# BLDC_Sch.net
KiCad netlist of a schematic drawn in Altium Designer
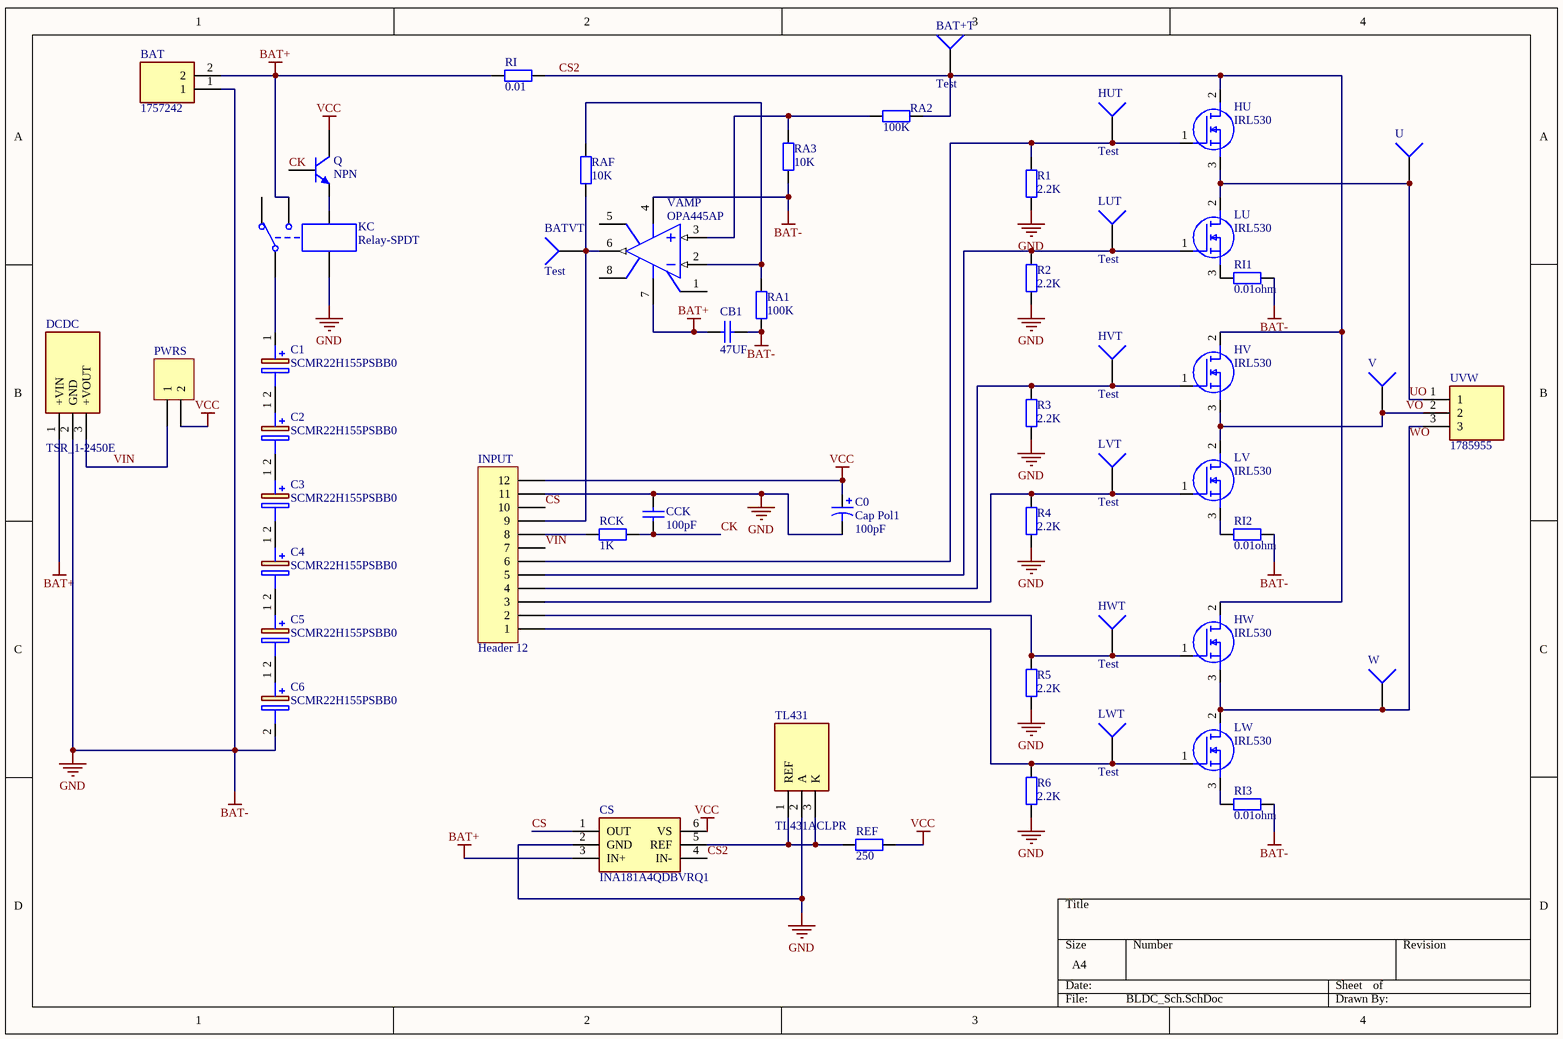
[diagram p0: BLDC_Sch.SchDoc]

(export (version "E")
  (design (tool "Eeschema 10.0.6"))
  (components
    (comp (ref "BAT")
      (value "1757242")
      (footprint "Comp_PCB:SHDR2W100P0X508_1X2_1016X860X1250P")
      (description "Connector")
      (fields
        (field (name "MANUFACTURER_PART_NUMBER") "OQ025A000000G")
        (field (name "MOUSER PART NUMBER") "523-OQ025A000000G")
      )
      (libsource (lib "Comp_Schm") (part "OQ025A000000G"))
    )
    (comp (ref "BAT+T")
      (value "Test")
      (footprint "PIN1")
      (description "Socket")
      (fields (field (name "PUBLISHER") "Altium Limited"))
      (libsource (lib "Miscellaneous Connectors") (part "Socket"))
    )
    (comp (ref "BATVT")
      (value "Test")
      (footprint "PIN1")
      (description "Socket")
      (fields (field (name "PUBLISHER") "Altium Limited"))
      (libsource (lib "Miscellaneous Connectors") (part "Socket"))
    )
    (comp (ref "C0")
      (value "Cap Pol1")
      (footprint "CAP 5.0*10*12.5")
      (description "Polarized Capacitor (Radial)")
      (fields (field (name "ALTIUM_VALUE") "100pF") (field (name "PUBLISHER") "Altium Limited"))
      (libsource (lib "Miscellaneous Devices") (part "Cap Pol1"))
    )
    (comp (ref "C1")
      (value "SCMR22H155PSBB0")
      (footprint "Comp_PCB:SCMR22H155PSBB0")
      (description "Capacitor Polarised")
      (fields (field (name "MOUSER PART NUMBER") "581-SCMR22H155PSBB0"))
      (libsource (lib "Comp_Schm") (part "SCMR22H155PSBB0"))
    )
    (comp (ref "C2")
      (value "SCMR22H155PSBB0")
      (footprint "Comp_PCB:SCMR22H155PSBB0")
      (description "Capacitor Polarised")
      (fields (field (name "MOUSER PART NUMBER") "581-SCMR22H155PSBB0"))
      (libsource (lib "Comp_Schm") (part "SCMR22H155PSBB0"))
    )
    (comp (ref "C3")
      (value "SCMR22H155PSBB0")
      (footprint "Comp_PCB:SCMR22H155PSBB0")
      (description "Capacitor Polarised")
      (fields (field (name "MOUSER PART NUMBER") "581-SCMR22H155PSBB0"))
      (libsource (lib "Comp_Schm") (part "SCMR22H155PSBB0"))
    )
    (comp (ref "C4")
      (value "SCMR22H155PSBB0")
      (footprint "Comp_PCB:SCMR22H155PSBB0")
      (description "Capacitor Polarised")
      (fields (field (name "MOUSER PART NUMBER") "581-SCMR22H155PSBB0"))
      (libsource (lib "Comp_Schm") (part "SCMR22H155PSBB0"))
    )
    (comp (ref "C5")
      (value "SCMR22H155PSBB0")
      (footprint "Comp_PCB:SCMR22H155PSBB0")
      (description "Capacitor Polarised")
      (fields (field (name "MOUSER PART NUMBER") "581-SCMR22H155PSBB0"))
      (libsource (lib "Comp_Schm") (part "SCMR22H155PSBB0"))
    )
    (comp (ref "C6")
      (value "SCMR22H155PSBB0")
      (footprint "Comp_PCB:SCMR22H155PSBB0")
      (description "Capacitor Polarised")
      (fields (field (name "MOUSER PART NUMBER") "581-SCMR22H155PSBB0"))
      (libsource (lib "Comp_Schm") (part "SCMR22H155PSBB0"))
    )
    (comp (ref "CB1")
      (value "47UF")
      (footprint "CBB 6.3*6.3*5")
      (description "Capacitor")
      (fields (field (name "Comment") "Cap") (field (name "PUBLISHER") "Altium Limited"))
      (libsource (lib "Miscellaneous Devices") (part "Cap"))
    )
    (comp (ref "CCK")
      (value "100pF")
      (footprint "CBB 6.3*6.3*5")
      (description "Capacitor")
      (fields (field (name "Comment") "Cap") (field (name "PUBLISHER") "Altium Limited"))
      (libsource (lib "Miscellaneous Devices") (part "Cap"))
    )
    (comp (ref "CS")
      (value "INA181A4QDBVRQ1")
      (footprint "Comp_PCB:SOT95P280X145-6N")
      (description "Integrated Circuit")
      (fields (field (name "MOUSER PART NUMBER") "595-INA181A4QDBVRQ1"))
      (libsource (lib "*") (part "INA181A4QDBVRQ1"))
    )
    (comp (ref "DCDC")
      (value "TSR_1-2450E")
      (footprint "Comp_PCB:TSR12450E")
      (description "Power Supply")
      (fields
        (field (name "MANUFACTURER_PART_NUMBER") "TSR 1-2450E")
        (field (name "MOUSER PART NUMBER") "495-TSR1-2450E")
      )
      (libsource (lib "*") (part "TSR_1-2450E"))
    )
    (comp (ref "HU")
      (value "IRL530")
      (footprint "Comp_PCB:TO254P465X1024X2050-3P")
      (description "MOSFET (N-Channel)")
      (fields (field (name "MOUSER PART NUMBER") "844-IRL530"))
      (libsource (lib "Comp_Schm") (part "IRL530"))
    )
    (comp (ref "HUT")
      (value "Test")
      (footprint "PIN1")
      (description "Socket")
      (fields (field (name "PUBLISHER") "Altium Limited"))
      (libsource (lib "Miscellaneous Connectors") (part "Socket"))
    )
    (comp (ref "HV")
      (value "IRL530")
      (footprint "Comp_PCB:TO254P465X1024X2050-3P")
      (description "MOSFET (N-Channel)")
      (fields (field (name "MOUSER PART NUMBER") "844-IRL530"))
      (libsource (lib "Comp_Schm") (part "IRL530"))
    )
    (comp (ref "HVT")
      (value "Test")
      (footprint "PIN1")
      (description "Socket")
      (fields (field (name "PUBLISHER") "Altium Limited"))
      (libsource (lib "Miscellaneous Connectors") (part "Socket"))
    )
    (comp (ref "HW")
      (value "IRL530")
      (footprint "Comp_PCB:TO254P465X1024X2050-3P")
      (description "MOSFET (N-Channel)")
      (fields (field (name "MOUSER PART NUMBER") "844-IRL530"))
      (libsource (lib "Comp_Schm") (part "IRL530"))
    )
    (comp (ref "HWT")
      (value "Test")
      (footprint "PIN1")
      (description "Socket")
      (fields (field (name "PUBLISHER") "Altium Limited"))
      (libsource (lib "Miscellaneous Connectors") (part "Socket"))
    )
    (comp (ref "INPUT")
      (value "Header 12")
      (footprint "HDR1X12")
      (description "Header, 12-Pin")
      (fields (field (name "PUBLISHER") "Altium Limited"))
      (libsource (lib "Miscellaneous Connectors") (part "Header 12"))
    )
    (comp (ref "KC")
      (value "Relay-SPDT")
      (footprint "SRD-C_BK")
      (description "Single-Pole Dual-Throw Relay")
      (fields (field (name "PUBLISHER") "Altium Limited"))
      (libsource (lib "Miscellaneous Devices") (part "Relay-SPDT"))
    )
    (comp (ref "LU")
      (value "IRL530")
      (footprint "Comp_PCB:TO254P465X1024X2050-3P")
      (description "MOSFET (N-Channel)")
      (fields (field (name "MOUSER PART NUMBER") "844-IRL530"))
      (libsource (lib "Comp_Schm") (part "IRL530"))
    )
    (comp (ref "LUT")
      (value "Test")
      (footprint "PIN1")
      (description "Socket")
      (fields (field (name "PUBLISHER") "Altium Limited"))
      (libsource (lib "Miscellaneous Connectors") (part "Socket"))
    )
    (comp (ref "LV")
      (value "IRL530")
      (footprint "Comp_PCB:TO254P465X1024X2050-3P")
      (description "MOSFET (N-Channel)")
      (fields (field (name "MOUSER PART NUMBER") "844-IRL530"))
      (libsource (lib "Comp_Schm") (part "IRL530"))
    )
    (comp (ref "LVT")
      (value "Test")
      (footprint "PIN1")
      (description "Socket")
      (fields (field (name "PUBLISHER") "Altium Limited"))
      (libsource (lib "Miscellaneous Connectors") (part "Socket"))
    )
    (comp (ref "LW")
      (value "IRL530")
      (footprint "Comp_PCB:TO254P465X1024X2050-3P")
      (description "MOSFET (N-Channel)")
      (fields (field (name "MOUSER PART NUMBER") "844-IRL530"))
      (libsource (lib "Comp_Schm") (part "IRL530"))
    )
    (comp (ref "LWT")
      (value "Test")
      (footprint "PIN1")
      (description "Socket")
      (fields (field (name "PUBLISHER") "Altium Limited"))
      (libsource (lib "Miscellaneous Connectors") (part "Socket"))
    )
    (comp (ref "PWRS")
      (value "Header 2")
      (footprint "HDR1X2")
      (description "Header, 2-Pin")
      (fields (field (name "PUBLISHER") "Altium Limited"))
      (libsource (lib "Miscellaneous Connectors") (part "Header 2"))
    )
    (comp (ref "Q")
      (value "NPN")
      (footprint "TO-226-AA")
      (description "NPN Bipolar Transistor")
      (fields (field (name "PUBLISHER") "Altium Limited"))
      (libsource (lib "Miscellaneous Devices") (part "NPN"))
    )
    (comp (ref "R1")
      (value "2.2K")
      (footprint "RS 1/4W")
      (description "Resistor")
      (fields (field (name "Comment") "Res2") (field (name "PUBLISHER") "Altium Limited"))
      (libsource (lib "") (part "Res2_2"))
    )
    (comp (ref "R2")
      (value "2.2K")
      (footprint "RS 1/4W")
      (description "Resistor")
      (fields (field (name "Comment") "Res2") (field (name "PUBLISHER") "Altium Limited"))
      (libsource (lib "") (part "Res2_2"))
    )
    (comp (ref "R3")
      (value "2.2K")
      (footprint "RS 1/4W")
      (description "Resistor")
      (fields (field (name "Comment") "Res2") (field (name "PUBLISHER") "Altium Limited"))
      (libsource (lib "") (part "Res2_2"))
    )
    (comp (ref "R4")
      (value "2.2K")
      (footprint "RS 1/4W")
      (description "Resistor")
      (fields (field (name "Comment") "Res2") (field (name "PUBLISHER") "Altium Limited"))
      (libsource (lib "") (part "Res2_1"))
    )
    (comp (ref "R5")
      (value "2.2K")
      (footprint "RS 1/4W")
      (description "Resistor")
      (fields (field (name "Comment") "Res2") (field (name "PUBLISHER") "Altium Limited"))
      (libsource (lib "") (part "Res2_1"))
    )
    (comp (ref "R6")
      (value "2.2K")
      (footprint "RS 1/4W")
      (description "Resistor")
      (fields (field (name "Comment") "Res2") (field (name "PUBLISHER") "Altium Limited"))
      (libsource (lib "") (part "Res2_1"))
    )
    (comp (ref "RA1")
      (value "100K")
      (footprint "RS 1/4W")
      (description "Resistor")
      (fields (field (name "Comment") "Res2") (field (name "PUBLISHER") "Altium Limited"))
      (libsource (lib "") (part "Res2_1"))
    )
    (comp (ref "RA2")
      (value "100K")
      (footprint "RS 1/4W")
      (description "Resistor")
      (fields (field (name "Comment") "Res2") (field (name "PUBLISHER") "Altium Limited"))
      (libsource (lib "Miscellaneous Devices") (part "Res2"))
    )
    (comp (ref "RA3")
      (value "10K")
      (footprint "RS 1/4W")
      (description "Resistor")
      (fields (field (name "Comment") "Res2") (field (name "PUBLISHER") "Altium Limited"))
      (libsource (lib "") (part "Res2_2"))
    )
    (comp (ref "RAF")
      (value "10K")
      (footprint "RS 1/4W")
      (description "Resistor")
      (fields (field (name "Comment") "Res2") (field (name "PUBLISHER") "Altium Limited"))
      (libsource (lib "") (part "Res2_2"))
    )
    (comp (ref "RCK")
      (value "1K")
      (footprint "RS 1/4W")
      (description "Resistor")
      (fields (field (name "Comment") "Res2") (field (name "PUBLISHER") "Altium Limited"))
      (libsource (lib "Miscellaneous Devices") (part "Res2"))
    )
    (comp (ref "REF")
      (value "250")
      (footprint "RS 1/4W")
      (description "Resistor")
      (fields (field (name "Comment") "Res2") (field (name "PUBLISHER") "Altium Limited"))
      (libsource (lib "Miscellaneous Devices") (part "Res2"))
    )
    (comp (ref "RI")
      (value "0.01")
      (footprint "R 2512")
      (description "Resistor")
      (fields (field (name "Comment") "Res2") (field (name "PUBLISHER") "Altium Limited"))
      (libsource (lib "Miscellaneous Devices") (part "Res2"))
    )
    (comp (ref "RI1")
      (value "0.01ohm")
      (footprint "R 2512")
      (description "Resistor")
      (fields (field (name "Comment") "Res2") (field (name "PUBLISHER") "Altium Limited"))
      (libsource (lib "Miscellaneous Devices") (part "Res2"))
    )
    (comp (ref "RI2")
      (value "0.01ohm")
      (footprint "R 2512")
      (description "Resistor")
      (fields (field (name "Comment") "Res2") (field (name "PUBLISHER") "Altium Limited"))
      (libsource (lib "Miscellaneous Devices") (part "Res2"))
    )
    (comp (ref "RI3")
      (value "0.01ohm")
      (footprint "R 2512")
      (description "Resistor")
      (fields (field (name "Comment") "Res2") (field (name "PUBLISHER") "Altium Limited"))
      (libsource (lib "Miscellaneous Devices") (part "Res2"))
    )
    (comp (ref "TL431")
      (value "TL431ACLPR")
      (footprint "Comp_PCB:TL431ACLPR")
      (description "Integrated Circuit")
      (fields (field (name "MOUSER PART NUMBER") "595-TL431ACLPR"))
      (libsource (lib "Comp_Schm") (part "TL431ACLPR"))
    )
    (comp (ref "U")
      (value "2376595-2")
      (footprint "23765952")
      (description "Socket")
      (fields (field (name "PUBLISHER") "Altium Limited"))
      (libsource (lib "Miscellaneous Connectors") (part "Socket"))
    )
    (comp (ref "UVW")
      (value "1785955")
      (footprint "Comp_PCB:SHDRRA3W103P0X508_1X3_1524X1200X872P")
      (description "Connector")
      (fields
        (field (name "MANUFACTURER_PART_NUMBER") "1759020")
        (field (name "MOUSER PART NUMBER") "651-1759020")
      )
      (libsource (lib "*") (part "1759020"))
    )
    (comp (ref "V")
      (value "2376595-2")
      (footprint "23765952")
      (description "Socket")
      (fields (field (name "PUBLISHER") "Altium Limited"))
      (libsource (lib "Miscellaneous Connectors") (part "Socket"))
    )
    (comp (ref "VAMP")
      (value "OPA445AP")
      (footprint "DIP794W53P254L959H508Q8N")
      (description "High Performance Operational Amplifier")
      (fields (field (name "PUBLISHER") "Altium Limited"))
      (libsource (lib "TI Operational Amplifier") (part "LM101AJG"))
    )
    (comp (ref "W")
      (value "2376595-2")
      (footprint "23765952")
      (description "Socket")
      (fields (field (name "PUBLISHER") "Altium Limited"))
      (libsource (lib "Miscellaneous Connectors") (part "Socket"))
    )
  )
  (nets
    (net (code "1") (name "/CK") (class "Default")
      (node (ref "CCK") (pin "1") (pinfunction "1_1") (pintype "passive"))
      (node (ref "Q") (pin "2") (pinfunction "B_2") (pintype "passive"))
      (node (ref "RCK") (pin "2") (pinfunction "2_2") (pintype "passive"))
    )
    (net (code "2") (name "/CS") (class "Default")
      (node (ref "CS") (pin "1") (pinfunction "OUT_1") (pintype "passive"))
      (node (ref "INPUT") (pin "10") (pinfunction "10_10") (pintype "passive"))
    )
    (net (code "3") (name "/CS2") (class "Default")
      (node (ref "BAT+T") (pin "1") (pinfunction "1_1") (pintype "passive"))
      (node (ref "CS") (pin "4") (pinfunction "IN-_4") (pintype "passive"))
      (node (ref "HU") (pin "2") (pinfunction "D_2") (pintype "passive"))
      (node (ref "HV") (pin "2") (pinfunction "D_2") (pintype "passive"))
      (node (ref "HW") (pin "2") (pinfunction "D_2") (pintype "passive"))
      (node (ref "RA2") (pin "2") (pinfunction "2_2") (pintype "passive"))
      (node (ref "RI") (pin "2") (pinfunction "2_2") (pintype "passive"))
    )
    (net (code "4") (name "/UO") (class "Default")
      (node (ref "HU") (pin "3") (pinfunction "S_3") (pintype "passive"))
      (node (ref "LU") (pin "2") (pinfunction "D_2") (pintype "passive"))
      (node (ref "U") (pin "1") (pinfunction "1_1") (pintype "passive"))
      (node (ref "UVW") (pin "1") (pinfunction "1_1") (pintype "passive"))
    )
    (net (code "5") (name "/VIN") (class "Default")
      (node (ref "DCDC") (pin "3") (pinfunction "+VOUT_3") (pintype "passive"))
      (node (ref "INPUT") (pin "7") (pinfunction "7_7") (pintype "passive"))
      (node (ref "PWRS") (pin "1") (pinfunction "1_1") (pintype "passive"))
    )
    (net (code "6") (name "/VO") (class "Default")
      (node (ref "HV") (pin "3") (pinfunction "S_3") (pintype "passive"))
      (node (ref "LV") (pin "2") (pinfunction "D_2") (pintype "passive"))
      (node (ref "UVW") (pin "2") (pinfunction "2_2") (pintype "passive"))
      (node (ref "V") (pin "1") (pinfunction "1_1") (pintype "passive"))
    )
    (net (code "7") (name "/WO") (class "Default")
      (node (ref "HW") (pin "3") (pinfunction "S_3") (pintype "passive"))
      (node (ref "LW") (pin "2") (pinfunction "D_2") (pintype "passive"))
      (node (ref "UVW") (pin "3") (pinfunction "3_3") (pintype "passive"))
      (node (ref "W") (pin "1") (pinfunction "1_1") (pintype "passive"))
    )
    (net (code "8") (name "BAT+") (class "Default")
      (node (ref "BAT") (pin "2") (pinfunction "2_2") (pintype "passive"))
      (node (ref "CB1") (pin "1") (pinfunction "1_1") (pintype "passive"))
      (node (ref "CS") (pin "3") (pinfunction "IN+_3") (pintype "passive"))
      (node (ref "DCDC") (pin "1") (pinfunction "+VIN_1") (pintype "passive"))
      (node (ref "KC") (pin "3") (pinfunction "3_3") (pintype "passive"))
      (node (ref "RI") (pin "1") (pinfunction "1_1") (pintype "passive"))
      (node (ref "VAMP") (pin "7") (pinfunction "V+_7") (pintype "power_in"))
    )
    (net (code "9") (name "BAT-") (class "Default")
      (node (ref "BAT") (pin "1") (pinfunction "1_1") (pintype "passive"))
      (node (ref "C0") (pin "2") (pinfunction "2_2") (pintype "passive"))
      (node (ref "C6") (pin "2") (pinfunction "-_2") (pintype "passive"))
      (node (ref "CB1") (pin "2") (pinfunction "2_2") (pintype "passive"))
      (node (ref "CCK") (pin "2") (pinfunction "2_2") (pintype "passive"))
      (node (ref "CS") (pin "2") (pinfunction "GND_2") (pintype "passive"))
      (node (ref "DCDC") (pin "2") (pinfunction "GND_2") (pintype "passive"))
      (node (ref "INPUT") (pin "11") (pinfunction "11_11") (pintype "passive"))
      (node (ref "KC") (pin "4") (pinfunction "4_4") (pintype "passive"))
      (node (ref "R1") (pin "1") (pinfunction "1_1") (pintype "passive"))
      (node (ref "R2") (pin "1") (pinfunction "1_1") (pintype "passive"))
      (node (ref "R3") (pin "1") (pinfunction "1_1") (pintype "passive"))
      (node (ref "R4") (pin "2") (pinfunction "2_2") (pintype "passive"))
      (node (ref "R5") (pin "2") (pinfunction "2_2") (pintype "passive"))
      (node (ref "R6") (pin "2") (pinfunction "2_2") (pintype "passive"))
      (node (ref "RA1") (pin "2") (pinfunction "2_2") (pintype "passive"))
      (node (ref "RA3") (pin "1") (pinfunction "1_1") (pintype "passive"))
      (node (ref "RI1") (pin "2") (pinfunction "2_2") (pintype "passive"))
      (node (ref "RI2") (pin "2") (pinfunction "2_2") (pintype "passive"))
      (node (ref "RI3") (pin "2") (pinfunction "2_2") (pintype "passive"))
      (node (ref "TL431") (pin "2") (pinfunction "A_2") (pintype "passive"))
      (node (ref "VAMP") (pin "4") (pinfunction "V-_4") (pintype "power_in"))
    )
    (net (code "10") (name "Net-(C1-+)") (class "Default")
      (node (ref "C1") (pin "1") (pinfunction "+_1") (pintype "passive"))
      (node (ref "KC") (pin "1") (pinfunction "1_1") (pintype "passive"))
    )
    (net (code "11") (name "Net-(C1--)") (class "Default")
      (node (ref "C1") (pin "2") (pinfunction "-_2") (pintype "passive"))
      (node (ref "C2") (pin "1") (pinfunction "+_1") (pintype "passive"))
    )
    (net (code "12") (name "Net-(C2--)") (class "Default")
      (node (ref "C2") (pin "2") (pinfunction "-_2") (pintype "passive"))
      (node (ref "C3") (pin "1") (pinfunction "+_1") (pintype "passive"))
    )
    (net (code "13") (name "Net-(C3--)") (class "Default")
      (node (ref "C3") (pin "2") (pinfunction "-_2") (pintype "passive"))
      (node (ref "C4") (pin "1") (pinfunction "+_1") (pintype "passive"))
    )
    (net (code "14") (name "Net-(C4--)") (class "Default")
      (node (ref "C4") (pin "2") (pinfunction "-_2") (pintype "passive"))
      (node (ref "C5") (pin "1") (pinfunction "+_1") (pintype "passive"))
    )
    (net (code "15") (name "Net-(C5--)") (class "Default")
      (node (ref "C5") (pin "2") (pinfunction "-_2") (pintype "passive"))
      (node (ref "C6") (pin "1") (pinfunction "+_1") (pintype "passive"))
    )
    (net (code "16") (name "Net-(CS-REF)") (class "Default")
      (node (ref "CS") (pin "5") (pinfunction "REF_5") (pintype "passive"))
      (node (ref "REF") (pin "1") (pinfunction "1_1") (pintype "passive"))
      (node (ref "TL431") (pin "1") (pinfunction "REF_1") (pintype "passive"))
      (node (ref "TL431") (pin "3") (pinfunction "K_3") (pintype "passive"))
    )
    (net (code "17") (name "Net-(HU-G)") (class "Default")
      (node (ref "HU") (pin "1") (pinfunction "G_1") (pintype "passive"))
      (node (ref "HUT") (pin "1") (pinfunction "1_1") (pintype "passive"))
      (node (ref "INPUT") (pin "6") (pinfunction "6_6") (pintype "passive"))
      (node (ref "R1") (pin "2") (pinfunction "2_2") (pintype "passive"))
    )
    (net (code "18") (name "Net-(HV-G)") (class "Default")
      (node (ref "HV") (pin "1") (pinfunction "G_1") (pintype "passive"))
      (node (ref "HVT") (pin "1") (pinfunction "1_1") (pintype "passive"))
      (node (ref "INPUT") (pin "4") (pinfunction "4_4") (pintype "passive"))
      (node (ref "R3") (pin "2") (pinfunction "2_2") (pintype "passive"))
    )
    (net (code "19") (name "Net-(HW-G)") (class "Default")
      (node (ref "HW") (pin "1") (pinfunction "G_1") (pintype "passive"))
      (node (ref "HWT") (pin "1") (pinfunction "1_1") (pintype "passive"))
      (node (ref "INPUT") (pin "2") (pinfunction "2_2") (pintype "passive"))
      (node (ref "R5") (pin "1") (pinfunction "1_1") (pintype "passive"))
    )
    (net (code "20") (name "Net-(INPUT-Pad8)") (class "Default")
      (node (ref "INPUT") (pin "8") (pinfunction "8_8") (pintype "passive"))
      (node (ref "RCK") (pin "1") (pinfunction "1_1") (pintype "passive"))
    )
    (net (code "21") (name "Net-(LU-G)") (class "Default")
      (node (ref "INPUT") (pin "5") (pinfunction "5_5") (pintype "passive"))
      (node (ref "LU") (pin "1") (pinfunction "G_1") (pintype "passive"))
      (node (ref "LUT") (pin "1") (pinfunction "1_1") (pintype "passive"))
      (node (ref "R2") (pin "2") (pinfunction "2_2") (pintype "passive"))
    )
    (net (code "22") (name "Net-(LU-S)") (class "Default")
      (node (ref "LU") (pin "3") (pinfunction "S_3") (pintype "passive"))
      (node (ref "RI1") (pin "1") (pinfunction "1_1") (pintype "passive"))
    )
    (net (code "23") (name "Net-(LV-G)") (class "Default")
      (node (ref "INPUT") (pin "3") (pinfunction "3_3") (pintype "passive"))
      (node (ref "LV") (pin "1") (pinfunction "G_1") (pintype "passive"))
      (node (ref "LVT") (pin "1") (pinfunction "1_1") (pintype "passive"))
      (node (ref "R4") (pin "1") (pinfunction "1_1") (pintype "passive"))
    )
    (net (code "24") (name "Net-(LV-S)") (class "Default")
      (node (ref "LV") (pin "3") (pinfunction "S_3") (pintype "passive"))
      (node (ref "RI2") (pin "1") (pinfunction "1_1") (pintype "passive"))
    )
    (net (code "25") (name "Net-(LW-G)") (class "Default")
      (node (ref "INPUT") (pin "1") (pinfunction "1_1") (pintype "passive"))
      (node (ref "LW") (pin "1") (pinfunction "G_1") (pintype "passive"))
      (node (ref "LWT") (pin "1") (pinfunction "1_1") (pintype "passive"))
      (node (ref "R6") (pin "1") (pinfunction "1_1") (pintype "passive"))
    )
    (net (code "26") (name "Net-(LW-S)") (class "Default")
      (node (ref "LW") (pin "3") (pinfunction "S_3") (pintype "passive"))
      (node (ref "RI3") (pin "1") (pinfunction "1_1") (pintype "passive"))
    )
    (net (code "27") (name "Net-(Q-E)") (class "Default")
      (node (ref "KC") (pin "5") (pinfunction "5_5") (pintype "passive"))
      (node (ref "Q") (pin "3") (pinfunction "E_3") (pintype "passive"))
    )
    (net (code "28") (name "Net-(VAMP-IN+)") (class "Default")
      (node (ref "RA2") (pin "1") (pinfunction "1_1") (pintype "passive"))
      (node (ref "RA3") (pin "2") (pinfunction "2_2") (pintype "passive"))
      (node (ref "VAMP") (pin "3") (pinfunction "IN+_3") (pintype "input"))
    )
    (net (code "29") (name "Net-(VAMP-IN-)") (class "Default")
      (node (ref "RA1") (pin "1") (pinfunction "1_1") (pintype "passive"))
      (node (ref "RAF") (pin "2") (pinfunction "2_2") (pintype "passive"))
      (node (ref "VAMP") (pin "2") (pinfunction "IN-_2") (pintype "input"))
    )
    (net (code "30") (name "Net-(VAMP-OUT)") (class "Default")
      (node (ref "BATVT") (pin "1") (pinfunction "1_1") (pintype "passive"))
      (node (ref "INPUT") (pin "9") (pinfunction "9_9") (pintype "passive"))
      (node (ref "RAF") (pin "1") (pinfunction "1_1") (pintype "passive"))
      (node (ref "VAMP") (pin "6") (pinfunction "OUT_6") (pintype "output"))
    )
    (net (code "31") (name "VCC") (class "Default")
      (node (ref "C0") (pin "1") (pinfunction "1_1") (pintype "passive"))
      (node (ref "CS") (pin "6") (pinfunction "VS_6") (pintype "passive"))
      (node (ref "INPUT") (pin "12") (pinfunction "12_12") (pintype "passive"))
      (node (ref "PWRS") (pin "2") (pinfunction "2_2") (pintype "passive"))
      (node (ref "Q") (pin "1") (pinfunction "C_1") (pintype "passive"))
      (node (ref "REF") (pin "2") (pinfunction "2_2") (pintype "passive"))
    )
    (net (code "32") (name "unconnected-(KC-Pad2)") (class "Default")
      (node (ref "KC") (pin "2") (pinfunction "2_2") (pintype "passive"))
    )
    (net (code "33") (name "unconnected-(VAMP-BAL1{slash}CMPEN-Pad1)") (class "Default")
      (node (ref "VAMP") (pin "1") (pinfunction "BAL1/CMPEN_1") (pintype "passive"))
    )
    (net (code "34") (name "unconnected-(VAMP-BAL2-Pad5)") (class "Default")
      (node (ref "VAMP") (pin "5") (pinfunction "BAL2_5") (pintype "passive"))
    )
    (net (code "35") (name "unconnected-(VAMP-CMPEN-Pad8)") (class "Default")
      (node (ref "VAMP") (pin "8") (pinfunction "CMPEN_8") (pintype "passive"))
    )
  )
)
